# 08-TYPE-C-PORT.net
KiCad netlist of a schematic drawn in Altium Designer
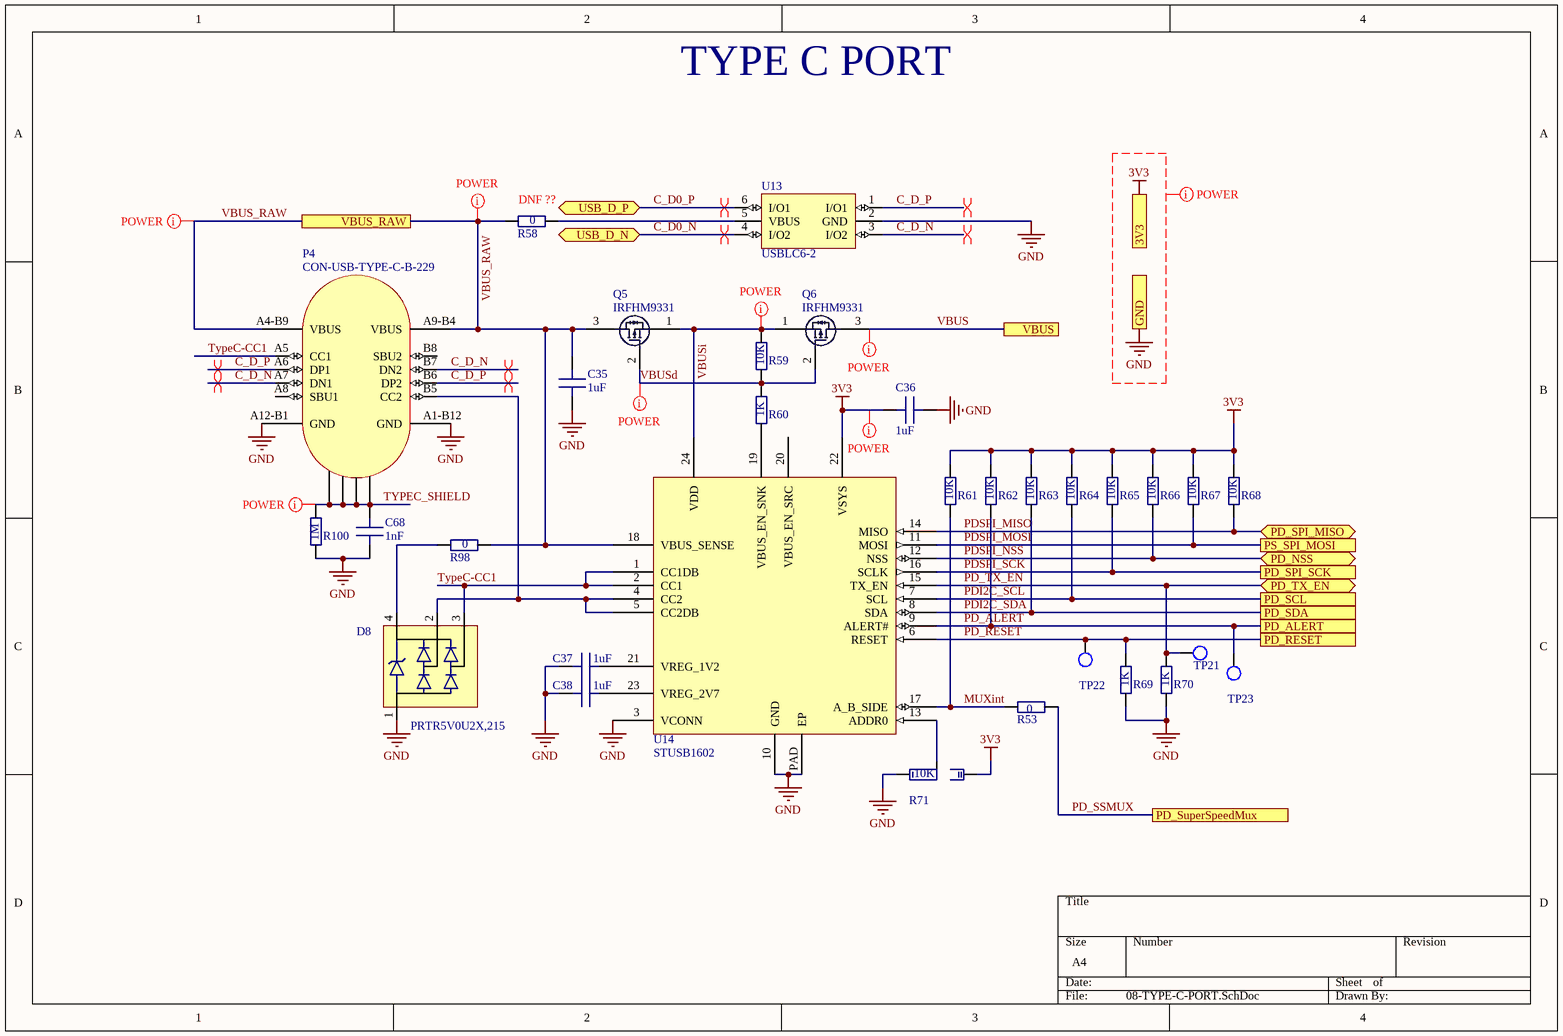
[diagram p0: 08-TYPE-C-PORT.SchDoc]

(export (version "E")
  (design (tool "Eeschema 10.0.6"))
  (components
    (comp (ref "C35")
      (value "1uF")
      (footprint "C0805")
      (description "Ceramic capacitor")
      (fields (field (name "VOLTAGE") "25V"))
      (libsource (lib "A.Shelestov_Capacitors") (part "C0805_1uF_25V"))
    )
    (comp (ref "C36")
      (value "1uF")
      (footprint "C0805")
      (description "Ceramic capacitor")
      (fields (field (name "VOLTAGE") "25V"))
      (libsource (lib "A.Shelestov_Capacitors") (part "C0805_1uF_25V"))
    )
    (comp (ref "C37")
      (value "1uF")
      (footprint "C0805")
      (description "Ceramic capacitor")
      (fields (field (name "VOLTAGE") "25V"))
      (libsource (lib "A.Shelestov_Capacitors") (part "C0805_1uF_25V"))
    )
    (comp (ref "C38")
      (value "1uF")
      (footprint "C0805")
      (description "Ceramic capacitor")
      (fields (field (name "VOLTAGE") "25V"))
      (libsource (lib "A.Shelestov_Capacitors") (part "C0805_1uF_25V"))
    )
    (comp (ref "C68")
      (value "1nF")
      (footprint "C1206")
      (description "Ceramic capacitor")
      (fields (field (name "VOLTAGE") "2KV"))
      (libsource (lib "A.Shelestov_Capacitors") (part "C1206_1nF_2KV"))
    )
    (comp (ref "D8")
      (value "PRTR5V0U2X,215")
      (footprint "SOT143B")
      (description "PRTR5V0U2X - Ultra low capacitance double rail-to-rail ESD protection diode")
      (fields (field (name "MF") "Nexperia USA"))
      (libsource (lib "ComponentsLib") (part "PRTR5V0U2X,215"))
    )
    (comp (ref "P4")
      (value "CON-USB-TYPE-C-B-229")
      (footprint "USB-Type-C-B-229")
      (libsource (lib "ComponentsLib") (part "CON-USB-TYPE-C-B-229"))
    )
    (comp (ref "Q5")
      (value "IRFHM9331")
      (footprint "PQFN-3x3")
      (libsource (lib "ComponentsLib") (part "IRFHM9331"))
    )
    (comp (ref "Q6")
      (value "IRFHM9331")
      (footprint "PQFN-3x3")
      (libsource (lib "ComponentsLib") (part "IRFHM9331"))
    )
    (comp (ref "R53")
      (value "~")
      (footprint "R0402")
      (description "Resistor General")
      (fields (field (name "RESISTANCE") "0"))
      (libsource (lib "A.Shelestov_Resistors") (part "R0402_0R"))
    )
    (comp (ref "R58")
      (value "~")
      (footprint "R0402_NOSILK")
      (description "Resistor General")
      (fields (field (name "RESISTANCE") "0"))
      (libsource (lib "A.Shelestov_Resistors") (part "R0402_0R"))
    )
    (comp (ref "R59")
      (value "~")
      (footprint "R0603")
      (description "Resistor General")
      (fields (field (name "TOLERANCE") "1%") (field (name "RESISTANCE") "10K"))
      (libsource (lib "A.Shelestov_Resistors") (part "R0603_10K_1%"))
    )
    (comp (ref "R60")
      (value "~")
      (footprint "R0603")
      (description "Resistor General")
      (fields (field (name "TOLERANCE") "1%") (field (name "RESISTANCE") "1K"))
      (libsource (lib "A.Shelestov_Resistors") (part "R0603_1K_1%"))
    )
    (comp (ref "R61")
      (value "~")
      (footprint "R0603")
      (description "Resistor General")
      (fields (field (name "TOLERANCE") "5%") (field (name "RESISTANCE") "10K"))
      (libsource (lib "A.Shelestov_Resistors") (part "R0603_10K"))
    )
    (comp (ref "R62")
      (value "~")
      (footprint "R0603")
      (description "Resistor General")
      (fields (field (name "TOLERANCE") "5%") (field (name "RESISTANCE") "10K"))
      (libsource (lib "A.Shelestov_Resistors") (part "R0603_10K"))
    )
    (comp (ref "R63")
      (value "~")
      (footprint "R0603")
      (description "Resistor General")
      (fields (field (name "TOLERANCE") "5%") (field (name "RESISTANCE") "10K"))
      (libsource (lib "A.Shelestov_Resistors") (part "R0603_10K"))
    )
    (comp (ref "R64")
      (value "~")
      (footprint "R0603")
      (description "Resistor General")
      (fields (field (name "TOLERANCE") "5%") (field (name "RESISTANCE") "10K"))
      (libsource (lib "A.Shelestov_Resistors") (part "R0603_10K"))
    )
    (comp (ref "R65")
      (value "~")
      (footprint "R0603")
      (description "Resistor General")
      (fields (field (name "TOLERANCE") "5%") (field (name "RESISTANCE") "10K"))
      (libsource (lib "A.Shelestov_Resistors") (part "R0603_10K"))
    )
    (comp (ref "R66")
      (value "~")
      (footprint "R0603")
      (description "Resistor General")
      (fields (field (name "TOLERANCE") "5%") (field (name "RESISTANCE") "10K"))
      (libsource (lib "A.Shelestov_Resistors") (part "R0603_10K"))
    )
    (comp (ref "R67")
      (value "~")
      (footprint "R0603")
      (description "Resistor General")
      (fields (field (name "TOLERANCE") "5%") (field (name "RESISTANCE") "10K"))
      (libsource (lib "A.Shelestov_Resistors") (part "R0603_10K"))
    )
    (comp (ref "R68")
      (value "~")
      (footprint "R0603")
      (description "Resistor General")
      (fields (field (name "TOLERANCE") "5%") (field (name "RESISTANCE") "10K"))
      (libsource (lib "A.Shelestov_Resistors") (part "R0603_10K"))
    )
    (comp (ref "R69")
      (value "~")
      (footprint "R0603")
      (description "Resistor General")
      (fields (field (name "TOLERANCE") "5%") (field (name "RESISTANCE") "1K"))
      (libsource (lib "A.Shelestov_Resistors") (part "R0603_1K"))
    )
    (comp (ref "R70")
      (value "~")
      (footprint "R0603")
      (description "Resistor General")
      (fields (field (name "TOLERANCE") "5%") (field (name "RESISTANCE") "1K"))
      (libsource (lib "A.Shelestov_Resistors") (part "R0603_1K"))
    )
    (comp (ref "R71")
      (value "~")
      (footprint "RJ0603")
      (description "Resistor General")
      (fields (field (name "TOLERANCE") "5%") (field (name "RESISTANCE") "10K"))
      (libsource (lib "A.Shelestov_Resistors") (part "RJ0603_10K"))
    )
    (comp (ref "R98")
      (value "~")
      (footprint "R0402")
      (description "Resistor General")
      (fields (field (name "RESISTANCE") "0"))
      (libsource (lib "A.Shelestov_Resistors") (part "R0402_0R"))
    )
    (comp (ref "R100")
      (value "~")
      (footprint "R2512")
      (description "Resistor General")
      (fields (field (name "TOLERANCE") "5%") (field (name "RESISTANCE") "1M"))
      (libsource (lib "A.Shelestov_Resistors") (part "R2512_1M_5%"))
    )
    (comp (ref "TP21")
      (value "TEST_POINT")
      (footprint "TP_1mm")
      (libsource (lib "ComponentsLib") (part "TEST_POINT"))
    )
    (comp (ref "TP22")
      (value "TEST_POINT")
      (footprint "TP_1mm")
      (libsource (lib "ComponentsLib") (part "TEST_POINT"))
    )
    (comp (ref "TP23")
      (value "TEST_POINT")
      (footprint "TP_1mm")
      (libsource (lib "ComponentsLib") (part "TEST_POINT"))
    )
    (comp (ref "U13")
      (value "USBLC6-2")
      (footprint "SOT-666")
      (description "Very low capacitance ESD protection")
      (libsource (lib "ComponentsLib") (part "USBLC6-2"))
    )
    (comp (ref "U14")
      (value "STUSB1602")
      (footprint "QFN24-4x4x0.9")
      (description "USB Type-C controller with TX/RX line driver and BMC")
      (libsource (lib "ComponentsLib") (part "STUSB1602"))
    )
  )
  (nets
    (net (code "1") (name "/C_D0_N") (class "Default")
      (node (ref "U13") (pin "4") (pinfunction "I/O2_4") (pintype "bidirectional"))
    )
    (net (code "2") (name "/C_D0_P") (class "Default")
      (node (ref "U13") (pin "6") (pinfunction "I/O1_6") (pintype "bidirectional"))
    )
    (net (code "3") (name "/C_D_N") (class "Default")
      (node (ref "P4") (pin "A7") (pinfunction "DN1_A7") (pintype "bidirectional"))
      (node (ref "P4") (pin "B7") (pinfunction "DN2_B7") (pintype "bidirectional"))
      (node (ref "U13") (pin "3") (pinfunction "I/O2_3") (pintype "bidirectional"))
    )
    (net (code "4") (name "/C_D_P") (class "Default")
      (node (ref "P4") (pin "A6") (pinfunction "DP1_A6") (pintype "bidirectional"))
      (node (ref "P4") (pin "B6") (pinfunction "DP2_B6") (pintype "bidirectional"))
      (node (ref "U13") (pin "1") (pinfunction "I/O1_1") (pintype "bidirectional"))
    )
    (net (code "5") (name "/MUXint") (class "Default")
      (node (ref "R53") (pin "2") (pinfunction "2_2") (pintype "passive"))
      (node (ref "R61") (pin "1") (pinfunction "1_1") (pintype "passive"))
      (node (ref "U14") (pin "17") (pinfunction "A_B_SIDE_17") (pintype "bidirectional"))
    )
    (net (code "6") (name "/PDI2C_SCL") (class "Default")
      (node (ref "R64") (pin "1") (pinfunction "1_1") (pintype "passive"))
      (node (ref "U14") (pin "7") (pinfunction "SCL_7") (pintype "input"))
    )
    (net (code "7") (name "/PDI2C_SDA") (class "Default")
      (node (ref "R63") (pin "1") (pinfunction "1_1") (pintype "passive"))
      (node (ref "U14") (pin "8") (pinfunction "SDA_8") (pintype "bidirectional"))
    )
    (net (code "8") (name "/PDSPI_MISO") (class "Default")
      (node (ref "R68") (pin "1") (pinfunction "1_1") (pintype "passive"))
      (node (ref "U14") (pin "14") (pinfunction "MISO_14") (pintype "input"))
    )
    (net (code "9") (name "/PDSPI_MOSI") (class "Default")
      (node (ref "R67") (pin "1") (pinfunction "1_1") (pintype "passive"))
      (node (ref "U14") (pin "11") (pinfunction "MOSI_11") (pintype "output"))
    )
    (net (code "10") (name "/PDSPI_NSS") (class "Default")
      (node (ref "R66") (pin "1") (pinfunction "1_1") (pintype "passive"))
      (node (ref "U14") (pin "12") (pinfunction "NSS_12") (pintype "bidirectional"))
    )
    (net (code "11") (name "/PDSPI_SCK") (class "Default")
      (node (ref "R65") (pin "1") (pinfunction "1_1") (pintype "passive"))
      (node (ref "U14") (pin "16") (pinfunction "SCLK_16") (pintype "output"))
    )
    (net (code "12") (name "/PD_ALERT") (class "Default")
      (node (ref "R62") (pin "1") (pinfunction "1_1") (pintype "passive"))
      (node (ref "TP23") (pin "1") (pinfunction "1_1") (pintype "passive"))
      (node (ref "U14") (pin "9") (pinfunction "ALERT#_9") (pintype "bidirectional"))
    )
    (net (code "13") (name "/PD_RESET") (class "Default")
      (node (ref "R69") (pin "2") (pinfunction "2_2") (pintype "passive"))
      (node (ref "TP22") (pin "1") (pinfunction "1_1") (pintype "passive"))
      (node (ref "U14") (pin "6") (pinfunction "RESET_6") (pintype "input"))
    )
    (net (code "14") (name "/PD_SSMUX") (class "Default")
      (node (ref "R53") (pin "1") (pinfunction "1_1") (pintype "passive"))
    )
    (net (code "15") (name "/PD_TX_EN") (class "Default")
      (node (ref "R70") (pin "2") (pinfunction "2_2") (pintype "passive"))
      (node (ref "TP21") (pin "1") (pinfunction "1_1") (pintype "passive"))
      (node (ref "U14") (pin "15") (pinfunction "TX_EN_15") (pintype "input"))
    )
    (net (code "16") (name "/TYPEC_SHIELD") (class "Default")
      (node (ref "C68") (pin "2") (pinfunction "2_2") (pintype "passive"))
      (node (ref "P4") (pin "SHIELD") (pinfunction "SHIELD_SHIELD") (pintype "power_in"))
      (node (ref "R100") (pin "2") (pinfunction "2_2") (pintype "passive"))
    )
    (net (code "17") (name "/TypeC-CC1") (class "Default")
      (node (ref "D8") (pin "3") (pinfunction "P$3_3") (pintype "passive"))
      (node (ref "P4") (pin "A5") (pinfunction "CC1_A5") (pintype "bidirectional"))
      (node (ref "U14") (pin "1") (pinfunction "CC1DB_1") (pintype "power_in"))
      (node (ref "U14") (pin "2") (pinfunction "CC1_2") (pintype "power_in"))
    )
    (net (code "18") (name "/VBUS") (class "Default")
      (node (ref "Q6") (pin "3") (pinfunction "D_3") (pintype "passive"))
    )
    (net (code "19") (name "/VBUS_RAW") (class "Default")
      (node (ref "C35") (pin "2") (pinfunction "2_2") (pintype "passive"))
      (node (ref "P4") (pin "A4-B9") (pinfunction "VBUS_A4-B9") (pintype "power_in"))
      (node (ref "P4") (pin "A9-B4") (pinfunction "VBUS_A9-B4") (pintype "power_in"))
      (node (ref "Q5") (pin "3") (pinfunction "D_3") (pintype "passive"))
      (node (ref "R58") (pin "1") (pinfunction "1_1") (pintype "passive"))
      (node (ref "R98") (pin "2") (pinfunction "2_2") (pintype "passive"))
      (node (ref "U14") (pin "18") (pinfunction "VBUS_SENSE_18") (pintype "power_in"))
    )
    (net (code "20") (name "/VBUSd") (class "Default")
      (node (ref "Q5") (pin "2") (pinfunction "G_2") (pintype "passive"))
      (node (ref "Q6") (pin "2") (pinfunction "G_2") (pintype "passive"))
      (node (ref "R59") (pin "1") (pinfunction "1_1") (pintype "passive"))
      (node (ref "R60") (pin "2") (pinfunction "2_2") (pintype "passive"))
    )
    (net (code "21") (name "/VBUSi") (class "Default")
      (node (ref "Q5") (pin "1") (pinfunction "S_1") (pintype "passive"))
      (node (ref "Q6") (pin "1") (pinfunction "S_1") (pintype "passive"))
      (node (ref "R59") (pin "2") (pinfunction "2_2") (pintype "passive"))
      (node (ref "U14") (pin "24") (pinfunction "VDD_24") (pintype "power_in"))
    )
    (net (code "22") (name "3V3") (class "Default")
      (node (ref "C36") (pin "1") (pinfunction "1_1") (pintype "passive"))
      (node (ref "R61") (pin "2") (pinfunction "2_2") (pintype "passive"))
      (node (ref "R62") (pin "2") (pinfunction "2_2") (pintype "passive"))
      (node (ref "R63") (pin "2") (pinfunction "2_2") (pintype "passive"))
      (node (ref "R64") (pin "2") (pinfunction "2_2") (pintype "passive"))
      (node (ref "R65") (pin "2") (pinfunction "2_2") (pintype "passive"))
      (node (ref "R66") (pin "2") (pinfunction "2_2") (pintype "passive"))
      (node (ref "R67") (pin "2") (pinfunction "2_2") (pintype "passive"))
      (node (ref "R68") (pin "2") (pinfunction "2_2") (pintype "passive"))
      (node (ref "R71") (pin "3") (pinfunction "3_3") (pintype "passive"))
      (node (ref "U14") (pin "22") (pinfunction "VSYS_22") (pintype "power_in"))
    )
    (net (code "23") (name "GND") (class "Default")
      (node (ref "C35") (pin "1") (pinfunction "1_1") (pintype "passive"))
      (node (ref "C36") (pin "2") (pinfunction "2_2") (pintype "passive"))
      (node (ref "C37") (pin "1") (pinfunction "1_1") (pintype "passive"))
      (node (ref "C38") (pin "1") (pinfunction "1_1") (pintype "passive"))
      (node (ref "C68") (pin "1") (pinfunction "1_1") (pintype "passive"))
      (node (ref "D8") (pin "1") (pinfunction "P$1_1") (pintype "passive"))
      (node (ref "P4") (pin "A1-B12") (pinfunction "GND_A1-B12") (pintype "power_in"))
      (node (ref "P4") (pin "A12-B1") (pinfunction "GND_A12-B1") (pintype "power_in"))
      (node (ref "R100") (pin "1") (pinfunction "1_1") (pintype "passive"))
      (node (ref "R69") (pin "1") (pinfunction "1_1") (pintype "passive"))
      (node (ref "R70") (pin "1") (pinfunction "1_1") (pintype "passive"))
      (node (ref "R71") (pin "1") (pinfunction "1_1") (pintype "passive"))
      (node (ref "U13") (pin "2") (pinfunction "GND_2") (pintype "power_in"))
      (node (ref "U14") (pin "10") (pinfunction "GND_10") (pintype "power_in"))
      (node (ref "U14") (pin "3") (pinfunction "VCONN_3") (pintype "power_in"))
      (node (ref "U14") (pin "PAD") (pinfunction "EP_PAD") (pintype "power_in"))
    )
    (net (code "24") (name "Net-(D8-P$2)") (class "Default")
      (node (ref "D8") (pin "2") (pinfunction "P$2_2") (pintype "passive"))
      (node (ref "P4") (pin "B5") (pinfunction "CC2_B5") (pintype "bidirectional"))
      (node (ref "U14") (pin "4") (pinfunction "CC2_4") (pintype "power_in"))
      (node (ref "U14") (pin "5") (pinfunction "CC2DB_5") (pintype "power_in"))
    )
    (net (code "25") (name "Net-(D8-P$4)") (class "Default")
      (node (ref "D8") (pin "4") (pinfunction "P$4_4") (pintype "passive"))
      (node (ref "R98") (pin "1") (pinfunction "1_1") (pintype "passive"))
    )
    (net (code "26") (name "Net-(U13-VBUS)") (class "Default")
      (node (ref "R58") (pin "2") (pinfunction "2_2") (pintype "passive"))
      (node (ref "U13") (pin "5") (pinfunction "VBUS_5") (pintype "power_in"))
    )
    (net (code "27") (name "Net-(U14-ADDR0)") (class "Default")
      (node (ref "R71") (pin "2") (pinfunction "2_2") (pintype "passive"))
      (node (ref "U14") (pin "13") (pinfunction "ADDR0_13") (pintype "input"))
    )
    (net (code "28") (name "Net-(U14-VBUS_EN_SNK)") (class "Default")
      (node (ref "R60") (pin "1") (pinfunction "1_1") (pintype "passive"))
      (node (ref "U14") (pin "19") (pinfunction "VBUS_EN_SNK_19") (pintype "power_in"))
    )
    (net (code "29") (name "Net-(U14-VREG_1V2)") (class "Default")
      (node (ref "C37") (pin "2") (pinfunction "2_2") (pintype "passive"))
      (node (ref "U14") (pin "21") (pinfunction "VREG_1V2_21") (pintype "power_in"))
    )
    (net (code "30") (name "Net-(U14-VREG_2V7)") (class "Default")
      (node (ref "C38") (pin "2") (pinfunction "2_2") (pintype "passive"))
      (node (ref "U14") (pin "23") (pinfunction "VREG_2V7_23") (pintype "power_in"))
    )
    (net (code "31") (name "unconnected-(P4-SBU1-PadA8)") (class "Default")
      (node (ref "P4") (pin "A8") (pinfunction "SBU1_A8") (pintype "bidirectional"))
    )
    (net (code "32") (name "unconnected-(P4-SBU2-PadB8)") (class "Default")
      (node (ref "P4") (pin "B8") (pinfunction "SBU2_B8") (pintype "bidirectional"))
    )
    (net (code "33") (name "unconnected-(U14-VBUS_EN_SRC-Pad20)") (class "Default")
      (node (ref "U14") (pin "20") (pinfunction "VBUS_EN_SRC_20") (pintype "power_in"))
    )
  )
)
